# lcd_mounting_board.net
KiCad netlist of a schematic drawn in EAGLE
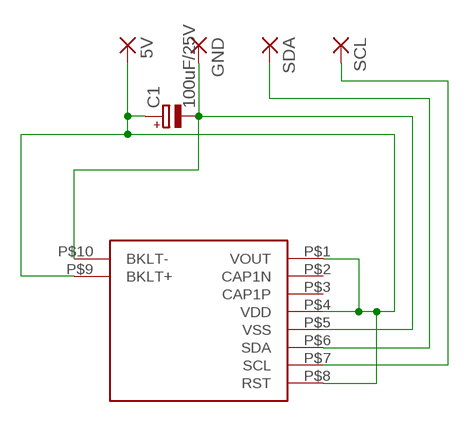
[diagram p0: schematic, sheet 1]

(export (version "E")
  (design (tool "Eeschema 10.0.6"))
  (components
    (comp (ref "5V")
      (value "2,15/1,0")
      (footprint "eagle-import:2,15_1,0")
      (libsource (lib "eagle-import") (part "2,15/1,0"))
    )
    (comp (ref "C1")
      (value "100uF/25V")
      (footprint "eagle-import:E2,5-6")
      (libsource (lib "eagle-import") (part "CPOL-EUE2.5-6"))
    )
    (comp (ref "GND")
      (value "2,15/1,0")
      (footprint "eagle-import:2,15_1,0")
      (libsource (lib "eagle-import") (part "2,15/1,0"))
    )
    (comp (ref "SCL")
      (value "2,15/1,0")
      (footprint "eagle-import:2,15_1,0")
      (libsource (lib "eagle-import") (part "2,15/1,0"))
    )
    (comp (ref "SDA")
      (value "2,15/1,0")
      (footprint "eagle-import:2,15_1,0")
      (libsource (lib "eagle-import") (part "2,15/1,0"))
    )
    (comp (ref "U$1")
      (value "MCCOG22005A6W-BNMLWI")
      (footprint "eagle-import:MCCOG22005A6W-BNMLWI")
      (libsource (lib "eagle-import") (part "MCCOG22005A6W-BNMLWI"))
    )
  )
  (nets
    (net (code "1") (name "Net-(5V-P)") (class "Default")
      (node (ref "5V") (pin "1") (pinfunction "P_1") (pintype "passive"))
      (node (ref "C1") (pin "+") (pinfunction "+_+") (pintype "passive"))
      (node (ref "U$1") (pin "P$1") (pinfunction "VOUT_P$1") (pintype "output"))
      (node (ref "U$1") (pin "P$4") (pinfunction "VDD_P$4") (pintype "power_in"))
      (node (ref "U$1") (pin "P$8") (pinfunction "RST_P$8") (pintype "input"))
      (node (ref "U$1") (pin "P$9") (pinfunction "BKLT+_P$9") (pintype "power_in"))
    )
    (net (code "2") (name "Net-(GND-P)") (class "Default")
      (node (ref "C1") (pin "-") (pinfunction "-_-") (pintype "passive"))
      (node (ref "GND") (pin "1") (pinfunction "P_1") (pintype "passive"))
      (node (ref "U$1") (pin "P$10") (pinfunction "BKLT-_P$10") (pintype "power_in"))
      (node (ref "U$1") (pin "P$5") (pinfunction "VSS_P$5") (pintype "power_in"))
    )
    (net (code "3") (name "Net-(SCL-P)") (class "Default")
      (node (ref "SCL") (pin "1") (pinfunction "P_1") (pintype "passive"))
      (node (ref "U$1") (pin "P$7") (pinfunction "SCL_P$7") (pintype "input"))
    )
    (net (code "4") (name "Net-(SDA-P)") (class "Default")
      (node (ref "SDA") (pin "1") (pinfunction "P_1") (pintype "passive"))
      (node (ref "U$1") (pin "P$6") (pinfunction "SDA_P$6") (pintype "input"))
    )
    (net (code "5") (name "unconnected-(U$1-CAP1N-PadP$2)") (class "Default")
      (node (ref "U$1") (pin "P$2") (pinfunction "CAP1N_P$2") (pintype "bidirectional"))
    )
    (net (code "6") (name "unconnected-(U$1-CAP1P-PadP$3)") (class "Default")
      (node (ref "U$1") (pin "P$3") (pinfunction "CAP1P_P$3") (pintype "bidirectional"))
    )
  )
)
